# 02-Nucleo_Breakout.net
KiCad netlist of a schematic drawn in Altium Designer
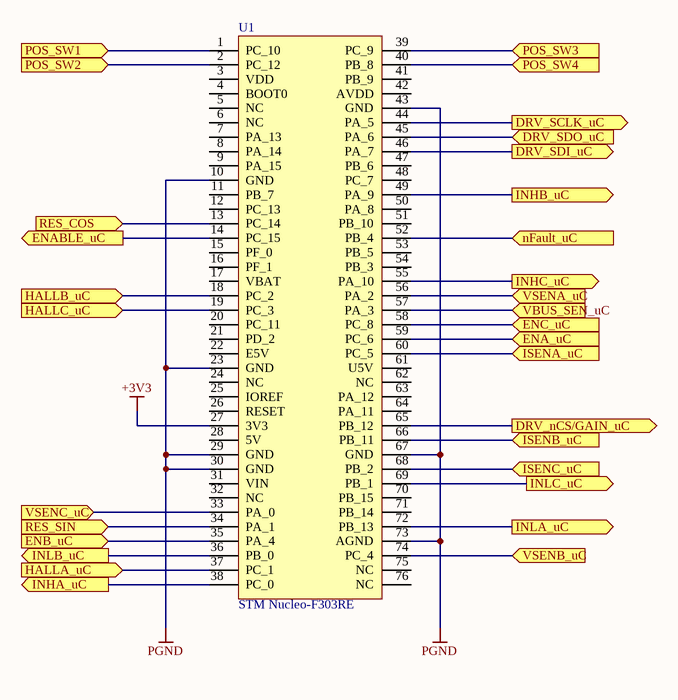
[diagram p0: 02-Nucleo_Breakout.SchDoc]

(export (version "E")
  (design (tool "Eeschema 10.0.6"))
  (components
    (comp (ref "U1")
      (value "STM Nucleo-F303RE")
      (footprint "Nucleo MORPHO CONNECTORS")
      (libsource (lib "driver_board_lib") (part "STM Nucleo-F303RE"))
    )
  )
  (nets
    (net (code "1") (name "+3V3") (class "Default")
      (node (ref "U1") (pin "27") (pinfunction "3V3_27") (pintype "passive"))
    )
    (net (code "2") (name "/DRV_SCLK_uC") (class "Default")
      (node (ref "U1") (pin "44") (pinfunction "PA_5_44") (pintype "passive"))
    )
    (net (code "3") (name "/DRV_SDI_uC") (class "Default")
      (node (ref "U1") (pin "46") (pinfunction "PA_7_46") (pintype "passive"))
    )
    (net (code "4") (name "/DRV_SDO_uC") (class "Default")
      (node (ref "U1") (pin "45") (pinfunction "PA_6_45") (pintype "passive"))
    )
    (net (code "5") (name "/DRV_nCS{slash}GAIN_uC") (class "Default")
      (node (ref "U1") (pin "65") (pinfunction "PB_12_65") (pintype "passive"))
    )
    (net (code "6") (name "/ENABLE_uC") (class "Default")
      (node (ref "U1") (pin "14") (pinfunction "PC_15_14") (pintype "passive"))
    )
    (net (code "7") (name "/ENA_uC") (class "Default")
      (node (ref "U1") (pin "59") (pinfunction "PC_6_59") (pintype "passive"))
    )
    (net (code "8") (name "/ENB_uC") (class "Default")
      (node (ref "U1") (pin "35") (pinfunction "PA_4_35") (pintype "passive"))
    )
    (net (code "9") (name "/ENC_uC") (class "Default")
      (node (ref "U1") (pin "58") (pinfunction "PC_8_58") (pintype "passive"))
    )
    (net (code "10") (name "/HALLA_uC") (class "Default")
      (node (ref "U1") (pin "37") (pinfunction "PC_1_37") (pintype "passive"))
    )
    (net (code "11") (name "/HALLB_uC") (class "Default")
      (node (ref "U1") (pin "18") (pinfunction "PC_2_18") (pintype "passive"))
    )
    (net (code "12") (name "/HALLC_uC") (class "Default")
      (node (ref "U1") (pin "19") (pinfunction "PC_3_19") (pintype "passive"))
    )
    (net (code "13") (name "/INHA_uC") (class "Default")
      (node (ref "U1") (pin "38") (pinfunction "PC_0_38") (pintype "passive"))
    )
    (net (code "14") (name "/INHB_uC") (class "Default")
      (node (ref "U1") (pin "49") (pinfunction "PA_9_49") (pintype "passive"))
    )
    (net (code "15") (name "/INHC_uC") (class "Default")
      (node (ref "U1") (pin "55") (pinfunction "PA_10_55") (pintype "passive"))
    )
    (net (code "16") (name "/INLA_uC") (class "Default")
      (node (ref "U1") (pin "72") (pinfunction "PB_13_72") (pintype "passive"))
    )
    (net (code "17") (name "/INLB_uC") (class "Default")
      (node (ref "U1") (pin "36") (pinfunction "PB_0_36") (pintype "passive"))
    )
    (net (code "18") (name "/INLC_uC") (class "Default")
      (node (ref "U1") (pin "69") (pinfunction "PB_1_69") (pintype "passive"))
    )
    (net (code "19") (name "/ISENA_uC") (class "Default")
      (node (ref "U1") (pin "60") (pinfunction "PC_5_60") (pintype "passive"))
    )
    (net (code "20") (name "/ISENB_uC") (class "Default")
      (node (ref "U1") (pin "66") (pinfunction "PB_11_66") (pintype "passive"))
    )
    (net (code "21") (name "/ISENC_uC") (class "Default")
      (node (ref "U1") (pin "68") (pinfunction "PB_2_68") (pintype "passive"))
    )
    (net (code "22") (name "/POS_SW1") (class "Default")
      (node (ref "U1") (pin "1") (pinfunction "PC_10_1") (pintype "passive"))
    )
    (net (code "23") (name "/POS_SW2") (class "Default")
      (node (ref "U1") (pin "2") (pinfunction "PC_12_2") (pintype "passive"))
    )
    (net (code "24") (name "/POS_SW3") (class "Default")
      (node (ref "U1") (pin "39") (pinfunction "PC_9_39") (pintype "passive"))
    )
    (net (code "25") (name "/POS_SW4") (class "Default")
      (node (ref "U1") (pin "40") (pinfunction "PB_8_40") (pintype "passive"))
    )
    (net (code "26") (name "/RES_COS") (class "Default")
      (node (ref "U1") (pin "13") (pinfunction "PC_14_13") (pintype "passive"))
    )
    (net (code "27") (name "/RES_SIN") (class "Default")
      (node (ref "U1") (pin "34") (pinfunction "PA_1_34") (pintype "passive"))
    )
    (net (code "28") (name "/VBUS_SEN_uC") (class "Default")
      (node (ref "U1") (pin "57") (pinfunction "PA_3_57") (pintype "passive"))
    )
    (net (code "29") (name "/VSENA_uC") (class "Default")
      (node (ref "U1") (pin "56") (pinfunction "PA_2_56") (pintype "passive"))
    )
    (net (code "30") (name "/VSENB_uC") (class "Default")
      (node (ref "U1") (pin "74") (pinfunction "PC_4_74") (pintype "passive"))
    )
    (net (code "31") (name "/VSENC_uC") (class "Default")
      (node (ref "U1") (pin "33") (pinfunction "PA_0_33") (pintype "passive"))
    )
    (net (code "32") (name "/nFault_uC") (class "Default")
      (node (ref "U1") (pin "52") (pinfunction "PB_4_52") (pintype "passive"))
    )
    (net (code "33") (name "PGND") (class "Default")
      (node (ref "U1") (pin "10") (pinfunction "GND_10") (pintype "passive"))
      (node (ref "U1") (pin "23") (pinfunction "GND_23") (pintype "passive"))
      (node (ref "U1") (pin "29") (pinfunction "GND_29") (pintype "passive"))
      (node (ref "U1") (pin "30") (pinfunction "GND_30") (pintype "passive"))
      (node (ref "U1") (pin "43") (pinfunction "GND_43") (pintype "passive"))
      (node (ref "U1") (pin "67") (pinfunction "GND_67") (pintype "passive"))
      (node (ref "U1") (pin "73") (pinfunction "AGND_73") (pintype "passive"))
    )
    (net (code "34") (name "unconnected-(U1-5V-Pad28)") (class "Default")
      (node (ref "U1") (pin "28") (pinfunction "5V_28") (pintype "passive"))
    )
    (net (code "35") (name "unconnected-(U1-AVDD-Pad42)") (class "Default")
      (node (ref "U1") (pin "42") (pinfunction "AVDD_42") (pintype "passive"))
    )
    (net (code "36") (name "unconnected-(U1-BOOT0-Pad4)") (class "Default")
      (node (ref "U1") (pin "4") (pinfunction "BOOT0_4") (pintype "passive"))
    )
    (net (code "37") (name "unconnected-(U1-E5V-Pad22)") (class "Default")
      (node (ref "U1") (pin "22") (pinfunction "E5V_22") (pintype "passive"))
    )
    (net (code "38") (name "unconnected-(U1-IOREF-Pad25)") (class "Default")
      (node (ref "U1") (pin "25") (pinfunction "IOREF_25") (pintype "passive"))
    )
    (net (code "39") (name "unconnected-(U1-NC-Pad5)") (class "Default")
      (node (ref "U1") (pin "5") (pinfunction "NC_5") (pintype "passive"))
    )
    (net (code "40") (name "unconnected-(U1-NC-Pad6)") (class "Default")
      (node (ref "U1") (pin "6") (pinfunction "NC_6") (pintype "passive"))
    )
    (net (code "41") (name "unconnected-(U1-NC-Pad24)") (class "Default")
      (node (ref "U1") (pin "24") (pinfunction "NC_24") (pintype "passive"))
    )
    (net (code "42") (name "unconnected-(U1-NC-Pad32)") (class "Default")
      (node (ref "U1") (pin "32") (pinfunction "NC_32") (pintype "passive"))
    )
    (net (code "43") (name "unconnected-(U1-NC-Pad62)") (class "Default")
      (node (ref "U1") (pin "62") (pinfunction "NC_62") (pintype "passive"))
    )
    (net (code "44") (name "unconnected-(U1-NC-Pad75)") (class "Default")
      (node (ref "U1") (pin "75") (pinfunction "NC_75") (pintype "passive"))
    )
    (net (code "45") (name "unconnected-(U1-NC-Pad76)") (class "Default")
      (node (ref "U1") (pin "76") (pinfunction "NC_76") (pintype "passive"))
    )
    (net (code "46") (name "unconnected-(U1-PA_8-Pad50)") (class "Default")
      (node (ref "U1") (pin "50") (pinfunction "PA_8_50") (pintype "passive"))
    )
    (net (code "47") (name "unconnected-(U1-PA_11-Pad64)") (class "Default")
      (node (ref "U1") (pin "64") (pinfunction "PA_11_64") (pintype "passive"))
    )
    (net (code "48") (name "unconnected-(U1-PA_12-Pad63)") (class "Default")
      (node (ref "U1") (pin "63") (pinfunction "PA_12_63") (pintype "passive"))
    )
    (net (code "49") (name "unconnected-(U1-PA_13-Pad7)") (class "Default")
      (node (ref "U1") (pin "7") (pinfunction "PA_13_7") (pintype "passive"))
    )
    (net (code "50") (name "unconnected-(U1-PA_14-Pad8)") (class "Default")
      (node (ref "U1") (pin "8") (pinfunction "PA_14_8") (pintype "passive"))
    )
    (net (code "51") (name "unconnected-(U1-PA_15-Pad9)") (class "Default")
      (node (ref "U1") (pin "9") (pinfunction "PA_15_9") (pintype "passive"))
    )
    (net (code "52") (name "unconnected-(U1-PB_3-Pad54)") (class "Default")
      (node (ref "U1") (pin "54") (pinfunction "PB_3_54") (pintype "passive"))
    )
    (net (code "53") (name "unconnected-(U1-PB_5-Pad53)") (class "Default")
      (node (ref "U1") (pin "53") (pinfunction "PB_5_53") (pintype "passive"))
    )
    (net (code "54") (name "unconnected-(U1-PB_6-Pad47)") (class "Default")
      (node (ref "U1") (pin "47") (pinfunction "PB_6_47") (pintype "passive"))
    )
    (net (code "55") (name "unconnected-(U1-PB_7-Pad11)") (class "Default")
      (node (ref "U1") (pin "11") (pinfunction "PB_7_11") (pintype "passive"))
    )
    (net (code "56") (name "unconnected-(U1-PB_9-Pad41)") (class "Default")
      (node (ref "U1") (pin "41") (pinfunction "PB_9_41") (pintype "passive"))
    )
    (net (code "57") (name "unconnected-(U1-PB_10-Pad51)") (class "Default")
      (node (ref "U1") (pin "51") (pinfunction "PB_10_51") (pintype "passive"))
    )
    (net (code "58") (name "unconnected-(U1-PB_14-Pad71)") (class "Default")
      (node (ref "U1") (pin "71") (pinfunction "PB_14_71") (pintype "passive"))
    )
    (net (code "59") (name "unconnected-(U1-PB_15-Pad70)") (class "Default")
      (node (ref "U1") (pin "70") (pinfunction "PB_15_70") (pintype "passive"))
    )
    (net (code "60") (name "unconnected-(U1-PC_7-Pad48)") (class "Default")
      (node (ref "U1") (pin "48") (pinfunction "PC_7_48") (pintype "passive"))
    )
    (net (code "61") (name "unconnected-(U1-PC_11-Pad20)") (class "Default")
      (node (ref "U1") (pin "20") (pinfunction "PC_11_20") (pintype "passive"))
    )
    (net (code "62") (name "unconnected-(U1-PC_13-Pad12)") (class "Default")
      (node (ref "U1") (pin "12") (pinfunction "PC_13_12") (pintype "passive"))
    )
    (net (code "63") (name "unconnected-(U1-PD_2-Pad21)") (class "Default")
      (node (ref "U1") (pin "21") (pinfunction "PD_2_21") (pintype "passive"))
    )
    (net (code "64") (name "unconnected-(U1-PF_0-Pad15)") (class "Default")
      (node (ref "U1") (pin "15") (pinfunction "PF_0_15") (pintype "passive"))
    )
    (net (code "65") (name "unconnected-(U1-PF_1-Pad16)") (class "Default")
      (node (ref "U1") (pin "16") (pinfunction "PF_1_16") (pintype "passive"))
    )
    (net (code "66") (name "unconnected-(U1-RESET-Pad26)") (class "Default")
      (node (ref "U1") (pin "26") (pinfunction "RESET_26") (pintype "passive"))
    )
    (net (code "67") (name "unconnected-(U1-U5V-Pad61)") (class "Default")
      (node (ref "U1") (pin "61") (pinfunction "U5V_61") (pintype "passive"))
    )
    (net (code "68") (name "unconnected-(U1-VBAT-Pad17)") (class "Default")
      (node (ref "U1") (pin "17") (pinfunction "VBAT_17") (pintype "passive"))
    )
    (net (code "69") (name "unconnected-(U1-VDD-Pad3)") (class "Default")
      (node (ref "U1") (pin "3") (pinfunction "VDD_3") (pintype "passive"))
    )
    (net (code "70") (name "unconnected-(U1-VIN-Pad31)") (class "Default")
      (node (ref "U1") (pin "31") (pinfunction "VIN_31") (pintype "passive"))
    )
  )
)
